# IV_transform_circuit.net
KiCad netlist of a schematic drawn in Altium Designer
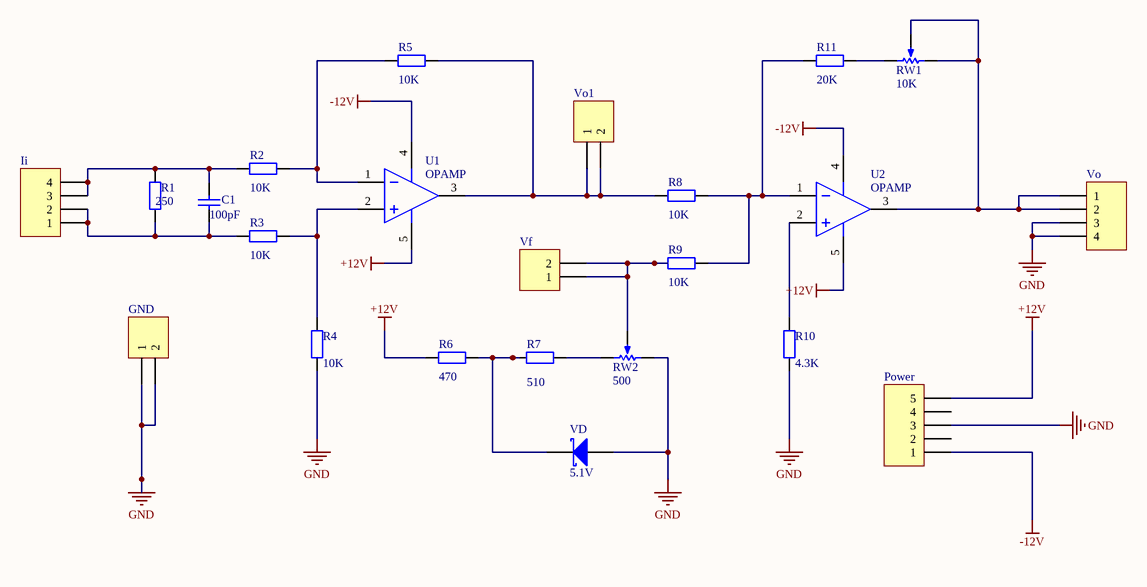
[diagram p0: IV_transform_circuit.SchDoc]

(export (version "E")
  (design (tool "Eeschema 10.0.6"))
  (components
    (comp (ref "C1")
      (value "100pF")
      (footprint "RAD-0.2")
      (description "Capacitor")
      (fields (field (name "Comment") "Cap") (field (name "PUBLISHER") "Altium Limited"))
      (libsource (lib "IV_transform_circuit") (part "Cap"))
    )
    (comp (ref "GND")
      (value "Header 2")
      (footprint "SIP-2")
      (description "Header, 2-Pin")
      (fields (field (name "PUBLISHER") "Altium Limited"))
      (libsource (lib "") (part "Header 2_1"))
    )
    (comp (ref "Ii")
      (value "Header 4")
      (footprint "SIP-4")
      (description "Header, 4-Pin")
      (fields (field (name "PUBLISHER") "Altium Limited"))
      (libsource (lib "") (part "Header 4_1"))
    )
    (comp (ref "Power")
      (value "Header 5")
      (footprint "POWER PLUG5")
      (description "Header, 5-Pin")
      (fields (field (name "PUBLISHER") "Altium Limited"))
      (libsource (lib "IV_transform_circuit") (part "Header 5"))
    )
    (comp (ref "R1")
      (value "250")
      (footprint "AXIAL-0.4")
      (description "Resistor")
      (fields (field (name "PUBLISHER") "Altium Limited"))
      (libsource (lib "") (part "Res2_2"))
    )
    (comp (ref "R2")
      (value "10K")
      (footprint "AXIAL-0.4")
      (description "Resistor")
      (fields (field (name "Comment") "Res2") (field (name "PUBLISHER") "Altium Limited"))
      (libsource (lib "IV_transform_circuit") (part "Res2"))
    )
    (comp (ref "R3")
      (value "10K")
      (footprint "AXIAL-0.4")
      (description "Resistor")
      (fields (field (name "Comment") "Res2") (field (name "PUBLISHER") "Altium Limited"))
      (libsource (lib "IV_transform_circuit") (part "Res2"))
    )
    (comp (ref "R4")
      (value "10K")
      (footprint "AXIAL-0.4")
      (description "Resistor")
      (fields (field (name "Comment") "Res2") (field (name "PUBLISHER") "Altium Limited"))
      (libsource (lib "") (part "Res2_1"))
    )
    (comp (ref "R5")
      (value "10K")
      (footprint "AXIAL-0.4")
      (description "Resistor")
      (fields (field (name "Comment") "Res2") (field (name "PUBLISHER") "Altium Limited"))
      (libsource (lib "IV_transform_circuit") (part "Res2"))
    )
    (comp (ref "R6")
      (value "470")
      (footprint "AXIAL-0.4")
      (description "Resistor")
      (fields (field (name "Comment") "Res2") (field (name "PUBLISHER") "Altium Limited"))
      (libsource (lib "IV_transform_circuit") (part "Res2"))
    )
    (comp (ref "R7")
      (value "510")
      (footprint "AXIAL-0.4")
      (description "Resistor")
      (fields (field (name "Comment") "Res2") (field (name "PUBLISHER") "Altium Limited"))
      (libsource (lib "IV_transform_circuit") (part "Res2"))
    )
    (comp (ref "R8")
      (value "10K")
      (footprint "AXIAL-0.4")
      (description "Resistor")
      (fields (field (name "Comment") "Res2") (field (name "PUBLISHER") "Altium Limited"))
      (libsource (lib "IV_transform_circuit") (part "Res2"))
    )
    (comp (ref "R9")
      (value "10K")
      (footprint "AXIAL-0.4")
      (description "Resistor")
      (fields (field (name "Comment") "Res2") (field (name "PUBLISHER") "Altium Limited"))
      (libsource (lib "IV_transform_circuit") (part "Res2"))
    )
    (comp (ref "R10")
      (value "4.3K")
      (footprint "AXIAL-0.4")
      (description "Resistor")
      (fields (field (name "Comment") "Res2") (field (name "PUBLISHER") "Altium Limited"))
      (libsource (lib "") (part "Res2_1"))
    )
    (comp (ref "R11")
      (value "20K")
      (footprint "AXIAL-0.4")
      (description "Resistor")
      (fields (field (name "Comment") "Res2") (field (name "PUBLISHER") "Altium Limited"))
      (libsource (lib "IV_transform_circuit") (part "Res2"))
    )
    (comp (ref "RW1")
      (value "10K")
      (footprint "VR5")
      (description "Potentiometer")
      (fields (field (name "Comment") "RPot") (field (name "PUBLISHER") "Altium Limited"))
      (libsource (lib "IV_transform_circuit") (part "RPot"))
    )
    (comp (ref "RW2")
      (value "500")
      (footprint "VR5")
      (description "Potentiometer")
      (fields (field (name "Comment") "RPot") (field (name "PUBLISHER") "Altium Limited"))
      (libsource (lib "IV_transform_circuit") (part "RPot"))
    )
    (comp (ref "U1")
      (value "OPAMP")
      (footprint "DIP-8")
      (description "Operational Amplifier")
      (libsource (lib "IV_transform_circuit") (part "OPAMP"))
    )
    (comp (ref "U2")
      (value "OPAMP")
      (footprint "DIP-8")
      (description "Operational Amplifier")
      (libsource (lib "IV_transform_circuit") (part "OPAMP"))
    )
    (comp (ref "VD")
      (value "5.1V")
      (footprint "DIODE-0.4")
      (description "Schottky Diode")
      (fields (field (name "PUBLISHER") "Altium Limited"))
      (libsource (lib "IV_transform_circuit") (part "D Schottky"))
    )
    (comp (ref "Vf")
      (value "Header 2")
      (footprint "SIP-2")
      (description "Header, 2-Pin")
      (fields (field (name "PUBLISHER") "Altium Limited"))
      (libsource (lib "IV_transform_circuit") (part "Header 2"))
    )
    (comp (ref "Vo")
      (value "Header 4")
      (footprint "SIP-4")
      (description "Header, 4-Pin")
      (fields (field (name "PUBLISHER") "Altium Limited"))
      (libsource (lib "IV_transform_circuit") (part "Header 4"))
    )
    (comp (ref "Vo1")
      (value "Header 2")
      (footprint "SIP-2")
      (description "Header, 2-Pin")
      (fields (field (name "PUBLISHER") "Altium Limited"))
      (libsource (lib "") (part "Header 2_1"))
    )
  )
  (nets
    (net (code "1") (name "+12V") (class "Default")
      (node (ref "Power") (pin "5") (pinfunction "5_5") (pintype "passive"))
      (node (ref "R6") (pin "2") (pinfunction "2_2") (pintype "passive"))
      (node (ref "U1") (pin "5") (pinfunction "V-_5") (pintype "passive"))
      (node (ref "U2") (pin "5") (pinfunction "V-_5") (pintype "passive"))
    )
    (net (code "2") (name "-12V") (class "Default")
      (node (ref "Power") (pin "1") (pinfunction "1_1") (pintype "passive"))
      (node (ref "U1") (pin "4") (pinfunction "V+_4") (pintype "passive"))
      (node (ref "U2") (pin "4") (pinfunction "V+_4") (pintype "passive"))
    )
    (net (code "3") (name "GND") (class "Default")
      (node (ref "GND") (pin "1") (pinfunction "1_1") (pintype "passive"))
      (node (ref "GND") (pin "2") (pinfunction "2_2") (pintype "passive"))
      (node (ref "Power") (pin "3") (pinfunction "3_3") (pintype "passive"))
      (node (ref "R10") (pin "2") (pinfunction "2_2") (pintype "passive"))
      (node (ref "R4") (pin "2") (pinfunction "2_2") (pintype "passive"))
      (node (ref "RW2") (pin "1") (pinfunction "TOP_1") (pintype "passive"))
      (node (ref "VD") (pin "1") (pinfunction "A_1") (pintype "passive"))
      (node (ref "Vo") (pin "3") (pinfunction "3_3") (pintype "passive"))
      (node (ref "Vo") (pin "4") (pinfunction "4_4") (pintype "passive"))
    )
    (net (code "4") (name "Net-(C1-Pad1)") (class "Default")
      (node (ref "C1") (pin "1") (pinfunction "1_1") (pintype "passive"))
      (node (ref "Ii") (pin "1") (pinfunction "1_1") (pintype "passive"))
      (node (ref "Ii") (pin "2") (pinfunction "2_2") (pintype "passive"))
      (node (ref "R1") (pin "1") (pinfunction "1_1") (pintype "passive"))
      (node (ref "R3") (pin "2") (pinfunction "2_2") (pintype "passive"))
    )
    (net (code "5") (name "Net-(C1-Pad2)") (class "Default")
      (node (ref "C1") (pin "2") (pinfunction "2_2") (pintype "passive"))
      (node (ref "Ii") (pin "3") (pinfunction "3_3") (pintype "passive"))
      (node (ref "Ii") (pin "4") (pinfunction "4_4") (pintype "passive"))
      (node (ref "R1") (pin "2") (pinfunction "2_2") (pintype "passive"))
      (node (ref "R2") (pin "2") (pinfunction "2_2") (pintype "passive"))
    )
    (net (code "6") (name "Net-(RW1-BOT)") (class "Default")
      (node (ref "R11") (pin "1") (pinfunction "1_1") (pintype "passive"))
      (node (ref "RW1") (pin "2") (pinfunction "BOT_2") (pintype "passive"))
    )
    (net (code "7") (name "Net-(RW1-TAP)") (class "Default")
      (node (ref "RW1") (pin "1") (pinfunction "TOP_1") (pintype "passive"))
      (node (ref "RW1") (pin "3") (pinfunction "TAP_3") (pintype "passive"))
      (node (ref "U2") (pin "3") (pinfunction "OUT_3") (pintype "passive"))
      (node (ref "Vo") (pin "1") (pinfunction "1_1") (pintype "passive"))
      (node (ref "Vo") (pin "2") (pinfunction "2_2") (pintype "passive"))
    )
    (net (code "8") (name "Net-(RW2-BOT)") (class "Default")
      (node (ref "R7") (pin "1") (pinfunction "1_1") (pintype "passive"))
      (node (ref "RW2") (pin "2") (pinfunction "BOT_2") (pintype "passive"))
    )
    (net (code "9") (name "Net-(RW2-TAP)") (class "Default")
      (node (ref "R9") (pin "2") (pinfunction "2_2") (pintype "passive"))
      (node (ref "RW2") (pin "3") (pinfunction "TAP_3") (pintype "passive"))
      (node (ref "Vf") (pin "1") (pinfunction "1_1") (pintype "passive"))
      (node (ref "Vf") (pin "2") (pinfunction "2_2") (pintype "passive"))
    )
    (net (code "10") (name "Net-(U1-IN+)") (class "Default")
      (node (ref "R3") (pin "1") (pinfunction "1_1") (pintype "passive"))
      (node (ref "R4") (pin "1") (pinfunction "1_1") (pintype "passive"))
      (node (ref "U1") (pin "2") (pinfunction "IN+_2") (pintype "passive"))
    )
    (net (code "11") (name "Net-(U1-IN-)") (class "Default")
      (node (ref "R2") (pin "1") (pinfunction "1_1") (pintype "passive"))
      (node (ref "R5") (pin "2") (pinfunction "2_2") (pintype "passive"))
      (node (ref "U1") (pin "1") (pinfunction "IN-_1") (pintype "passive"))
    )
    (net (code "12") (name "Net-(U1-OUT)") (class "Default")
      (node (ref "R5") (pin "1") (pinfunction "1_1") (pintype "passive"))
      (node (ref "R8") (pin "2") (pinfunction "2_2") (pintype "passive"))
      (node (ref "U1") (pin "3") (pinfunction "OUT_3") (pintype "passive"))
      (node (ref "Vo1") (pin "1") (pinfunction "1_1") (pintype "passive"))
      (node (ref "Vo1") (pin "2") (pinfunction "2_2") (pintype "passive"))
    )
    (net (code "13") (name "Net-(U2-IN+)") (class "Default")
      (node (ref "R10") (pin "1") (pinfunction "1_1") (pintype "passive"))
      (node (ref "U2") (pin "2") (pinfunction "IN+_2") (pintype "passive"))
    )
    (net (code "14") (name "Net-(U2-IN-)") (class "Default")
      (node (ref "R11") (pin "2") (pinfunction "2_2") (pintype "passive"))
      (node (ref "R8") (pin "1") (pinfunction "1_1") (pintype "passive"))
      (node (ref "R9") (pin "1") (pinfunction "1_1") (pintype "passive"))
      (node (ref "U2") (pin "1") (pinfunction "IN-_1") (pintype "passive"))
    )
    (net (code "15") (name "Net-(VD-K)") (class "Default")
      (node (ref "R6") (pin "1") (pinfunction "1_1") (pintype "passive"))
      (node (ref "R7") (pin "2") (pinfunction "2_2") (pintype "passive"))
      (node (ref "VD") (pin "2") (pinfunction "K_2") (pintype "passive"))
    )
    (net (code "16") (name "unconnected-(Power-Pad2)") (class "Default")
      (node (ref "Power") (pin "2") (pinfunction "2_2") (pintype "passive"))
    )
    (net (code "17") (name "unconnected-(Power-Pad4)") (class "Default")
      (node (ref "Power") (pin "4") (pinfunction "4_4") (pintype "passive"))
    )
  )
)
